# radio_module.net
KiCad netlist of a schematic drawn in Altium Designer
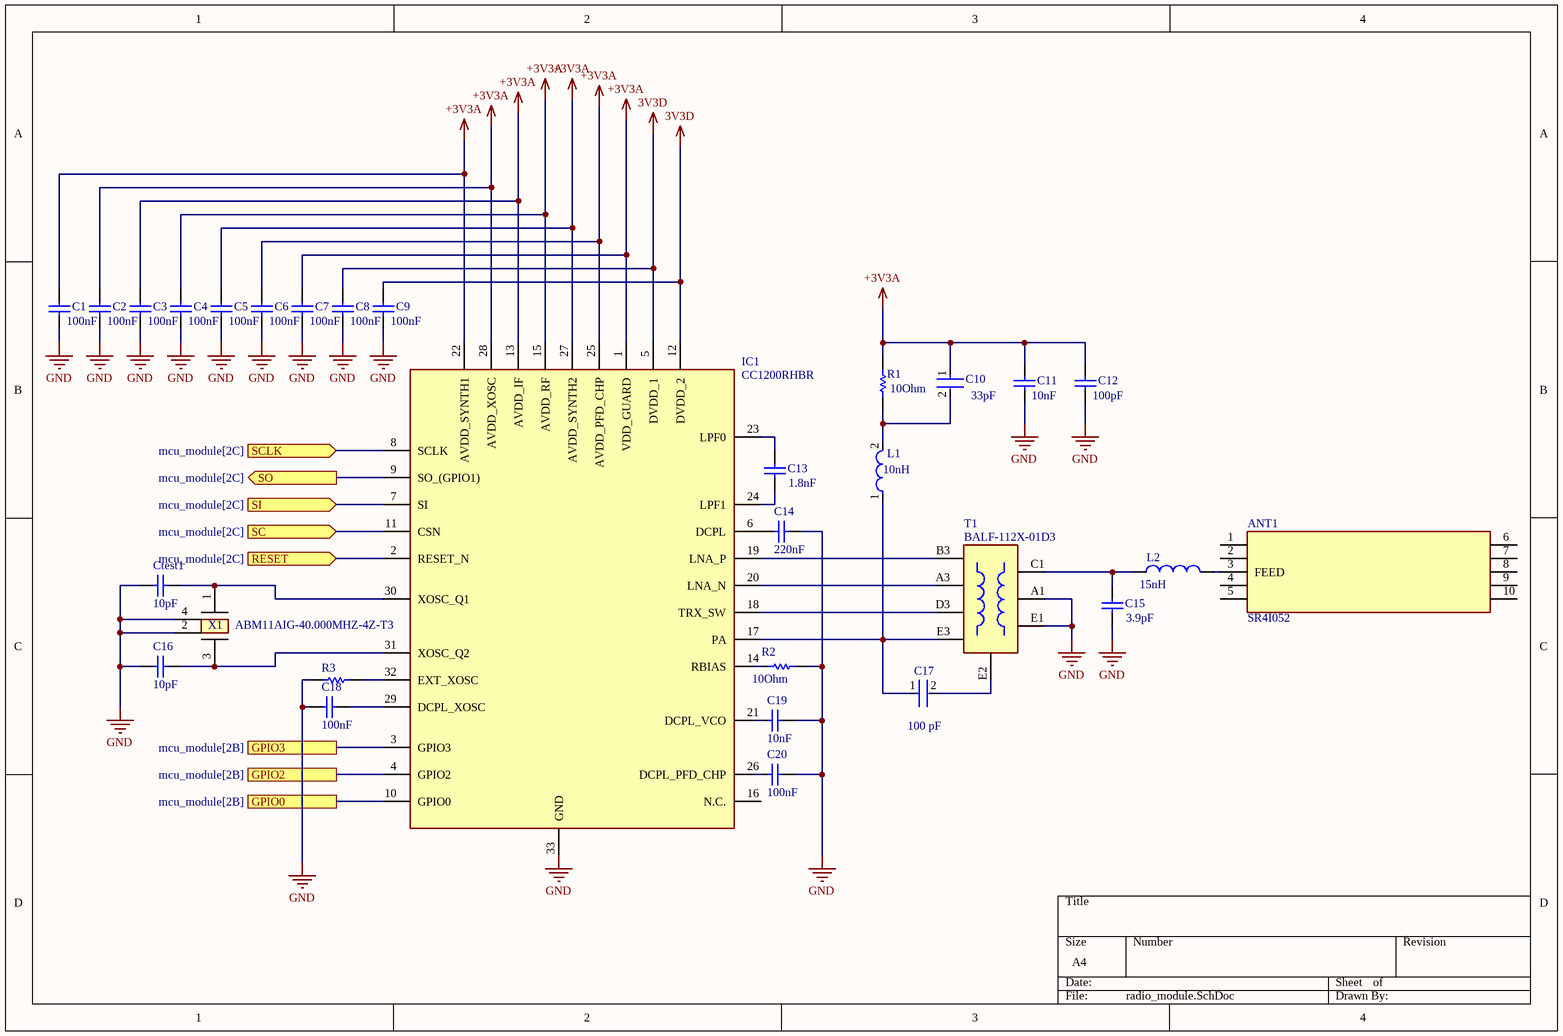
[diagram p0: radio_module.SchDoc]

(export (version "E")
  (design (tool "Eeschema 10.0.6"))
  (components
    (comp (ref "ANT1")
      (value "SR4I052")
      (footprint "SamacSys:SR4I052")
      (description "Antenna")
      (fields (field (name "MOUSER PART NUMBER") "237-SR4I052"))
      (libsource (lib "*") (part "SR4I052"))
    )
    (comp (ref "C1")
      (value "100nF")
      (footprint "CAPC1608X92X38LL15T08")
      (fields (field (name "MANUFACTURER") "Vitramon") (field (name "PART NUMBER") "VJ0603D3R9CXPAJ"))
      (libsource (lib "Altium Content Vault") (part "CAP"))
    )
    (comp (ref "C2")
      (value "100nF")
      (footprint "CAPC1608X92X38LL15T08")
      (fields (field (name "MANUFACTURER") "Vitramon") (field (name "PART NUMBER") "VJ0603D3R9CXPAJ"))
      (libsource (lib "Altium Content Vault") (part "CAP"))
    )
    (comp (ref "C3")
      (value "100nF")
      (footprint "CAPC1608X92X38LL15T08")
      (fields (field (name "MANUFACTURER") "Vitramon") (field (name "PART NUMBER") "VJ0603D3R9CXPAJ"))
      (libsource (lib "Altium Content Vault") (part "CAP"))
    )
    (comp (ref "C4")
      (value "100nF")
      (footprint "CAPC1608X92X38LL15T08")
      (fields (field (name "MANUFACTURER") "Vitramon") (field (name "PART NUMBER") "VJ0603D3R9CXPAJ"))
      (libsource (lib "Altium Content Vault") (part "CAP"))
    )
    (comp (ref "C5")
      (value "100nF")
      (footprint "CAPC1608X92X38LL15T08")
      (fields (field (name "MANUFACTURER") "Vitramon") (field (name "PART NUMBER") "VJ0603D3R9CXPAJ"))
      (libsource (lib "Altium Content Vault") (part "CAP"))
    )
    (comp (ref "C6")
      (value "100nF")
      (footprint "CAPC1608X92X38LL15T08")
      (fields (field (name "MANUFACTURER") "Vitramon") (field (name "PART NUMBER") "VJ0603D3R9CXPAJ"))
      (libsource (lib "Altium Content Vault") (part "CAP"))
    )
    (comp (ref "C7")
      (value "100nF")
      (footprint "CAPC1608X92X38LL15T08")
      (fields (field (name "MANUFACTURER") "Vitramon") (field (name "PART NUMBER") "VJ0603D3R9CXPAJ"))
      (libsource (lib "Altium Content Vault") (part "CAP"))
    )
    (comp (ref "C8")
      (value "100nF")
      (footprint "CAPC1608X92X38LL15T08")
      (fields (field (name "MANUFACTURER") "Vitramon") (field (name "PART NUMBER") "VJ0603D3R9CXPAJ"))
      (libsource (lib "Altium Content Vault") (part "CAP"))
    )
    (comp (ref "C9")
      (value "100nF")
      (footprint "CAPC1608X92X38LL15T08")
      (fields (field (name "MANUFACTURER") "Vitramon") (field (name "PART NUMBER") "VJ0603D3R9CXPAJ"))
      (libsource (lib "Altium Content Vault") (part "CAP"))
    )
    (comp (ref "C10")
      (value "33pF")
      (footprint "FP-C0402-BB-MFG")
      (description "CAP CER 0.1UF 16V X7R 0402")
      (fields
        (field (name "TOLERANCE") "0.1")
        (field (name "OCTOPART") "https://octopart.com/c0402c104k4ractu-kemet-94158")
      )
      (libsource (lib "Altium Content Vault") (part "b4654b650e69147ec39a6b967a45e02"))
    )
    (comp (ref "C11")
      (value "10nF")
      (footprint "CAPC1608X92X38LL15T08")
      (fields (field (name "MANUFACTURER") "Vitramon") (field (name "PART NUMBER") "VJ0603D3R9CXPAJ"))
      (libsource (lib "Altium Content Vault") (part "CAP"))
    )
    (comp (ref "C12")
      (value "100pF")
      (footprint "CAPC1608X92X38LL15T08")
      (fields (field (name "MANUFACTURER") "Vitramon") (field (name "PART NUMBER") "VJ0603D3R9CXPAJ"))
      (libsource (lib "Altium Content Vault") (part "CAP"))
    )
    (comp (ref "C13")
      (value "1.8nF")
      (footprint "CAPC1608X92X38LL15T08")
      (fields (field (name "MANUFACTURER") "Vitramon") (field (name "PART NUMBER") "VJ0603D3R9CXPAJ"))
      (libsource (lib "Altium Content Vault") (part "CAP"))
    )
    (comp (ref "C14")
      (value "220nF")
      (footprint "CAPC1608X92X38LL15T08")
      (fields (field (name "MANUFACTURER") "Vitramon") (field (name "PART NUMBER") "VJ0603D3R9CXPAJ"))
      (libsource (lib "Altium Content Vault") (part "CAP"))
    )
    (comp (ref "C15")
      (value "3.9pF")
      (footprint "CAPC1608X92X38LL15T08")
      (fields (field (name "MANUFACTURER") "Vitramon") (field (name "PART NUMBER") "VJ0603D3R9CXPAJ"))
      (libsource (lib "Altium Content Vault") (part "CAP"))
    )
    (comp (ref "C16")
      (value "10pF")
      (footprint "CAPC1608X92X38LL15T08")
      (fields (field (name "MANUFACTURER") "Vitramon") (field (name "PART NUMBER") "VJ0603D3R9CXPAJ"))
      (libsource (lib "Altium Content Vault") (part "CAP"))
    )
    (comp (ref "C17")
      (value "C0402C101J5GACTU")
      (footprint "FP-C0402-BB-MFG")
      (description "CAP CER 100PF 50V C0G/NP0 0402")
      (fields
        (field (name "MANUFACTURER") "Kemet")
        (field (name "TOLERANCE") "0.05")
        (field (name "CAPACITANCE") "100 pF")
      )
      (libsource (lib "Altium Content Vault") (part "b4654b650e69147ec39a6b967a45e02"))
    )
    (comp (ref "C18")
      (value "100nF")
      (footprint "CAPC1608X92X38LL15T08")
      (fields (field (name "MANUFACTURER") "Vitramon") (field (name "PART NUMBER") "VJ0603D3R9CXPAJ"))
      (libsource (lib "Altium Content Vault") (part "CAP"))
    )
    (comp (ref "C19")
      (value "10nF")
      (footprint "CAPC1608X92X38LL15T08")
      (fields (field (name "MANUFACTURER") "Vitramon") (field (name "PART NUMBER") "VJ0603D3R9CXPAJ"))
      (libsource (lib "Altium Content Vault") (part "CAP"))
    )
    (comp (ref "C20")
      (value "100nF")
      (footprint "CAPC1608X92X38LL15T08")
      (fields (field (name "MANUFACTURER") "Vitramon") (field (name "PART NUMBER") "VJ0603D3R9CXPAJ"))
      (libsource (lib "Altium Content Vault") (part "CAP"))
    )
    (comp (ref "Ctest1")
      (value "10pF")
      (footprint "CAPC1608X92X38LL15T08")
      (fields (field (name "MANUFACTURER") "Vitramon") (field (name "PART NUMBER") "VJ0603D3R9CXPAJ"))
      (libsource (lib "Altium Content Vault") (part "CAP"))
    )
    (comp (ref "IC1")
      (value "CC1200RHBR")
      (footprint "SamacSys:QFN50P500X500X100-33N-D")
      (description "Integrated Circuit")
      (fields (field (name "MOUSER PART NUMBER") "595-CC1200RHBR"))
      (libsource (lib "SamacSys") (part "CC1200RHBR"))
    )
    (comp (ref "L1")
      (value "LQW15AN10NH00D")
      (footprint "FP-LQW15AN_00-W0_6-0_1-MFG")
      (description "Wire Wound RF Inductor 10nH ±3% 500mA 0.17Ω 0402 (1005)")
      (fields (field (name "INDUCTANCE") "10nH") (field (name "TOLERANCE") "3%"))
      (libsource (lib "Altium Content Vault") (part "725321dda6339637d4d059423bc1c3c"))
    )
    (comp (ref "L2")
      (value "7447860115G")
      (footprint "WE-MK_0603_L1.6W0.8H0.8")
      (description "7447860115G Multilayer Inductor, 15Nh, 0.3A, 0603 Rohs Compliant: Yes")
      (fields (field (name "INDUCTANCE") "15nH"))
      (libsource (lib "Altium Content Vault") (part "Inductor - 1"))
    )
    (comp (ref "R1")
      (value "10Ohm")
      (footprint "RESC1005X40X25NL05T05")
      (fields (field (name "PART NUMBER") "CRCW040210R0FKED") (field (name "MANUFACTURER") "Vishay Dale"))
      (libsource (lib "Altium Content Vault") (part "RES"))
    )
    (comp (ref "R2")
      (value "RC0603JR-070RL")
      (footprint "RESC1608X55X25ML10T15")
      (description "Chip Resistor, 0 Ohm, +/- 5%, 0.1 W, -55 to 155 degC, 0603 (1608 Metric), RoHS, Tape and Reel")
      (fields
        (field (name "TOLERANCE") "5%")
        (field (name "RESISTANCE") "10Ohm")
        (field (name "MANUFACTURER") "Yageo")
      )
      (libsource (lib "Altium Content Vault") (part "RES-2"))
    )
    (comp (ref "R3")
      (value "RC0603JR-070RL")
      (footprint "RESC1608X55X25ML10T15")
      (description "Chip Resistor, 0 Ohm, +/- 5%, 0.1 W, -55 to 155 degC, 0603 (1608 Metric), RoHS, Tape and Reel")
      (fields (field (name "TOLERANCE") "5%") (field (name "MANUFACTURER") "Yageo"))
      (libsource (lib "Altium Content Vault") (part "RES-2"))
    )
    (comp (ref "T1")
      (value "BALF-112X-01D3")
      (footprint "SamacSys:BALF112X01D3")
      (description "Transformer")
      (fields (field (name "MOUSER PART NUMBER") "511-BALF-112X-01D3"))
      (libsource (lib "SamacSys") (part "BALF-112X-01D3"))
    )
    (comp (ref "X1")
      (value "ABM11AIG-40.000MHZ-4Z-T3")
      (footprint "SamacSys:ABM11AIG16000MHZ81ZT")
      (description "Crystal or Oscillator")
      (fields (field (name "MOUSER PART NUMBER") "815-M11AIG-40-4ZT3"))
      (libsource (lib "SamacSys") (part "ABM11AIG-40.000MHZ-4Z-T3"))
    )
  )
  (nets
    (net (code "1") (name "+3V3A") (class "Default")
      (node (ref "C1") (pin "2") (pinfunction "2_2") (pintype "passive"))
      (node (ref "C10") (pin "1") (pinfunction "1_1") (pintype "passive"))
      (node (ref "C11") (pin "2") (pinfunction "2_2") (pintype "passive"))
      (node (ref "C12") (pin "2") (pinfunction "2_2") (pintype "passive"))
      (node (ref "C2") (pin "2") (pinfunction "2_2") (pintype "passive"))
      (node (ref "C3") (pin "2") (pinfunction "2_2") (pintype "passive"))
      (node (ref "C4") (pin "2") (pinfunction "2_2") (pintype "passive"))
      (node (ref "C5") (pin "2") (pinfunction "2_2") (pintype "passive"))
      (node (ref "C6") (pin "2") (pinfunction "2_2") (pintype "passive"))
      (node (ref "C7") (pin "2") (pinfunction "2_2") (pintype "passive"))
      (node (ref "IC1") (pin "1") (pinfunction "VDD_GUARD_1") (pintype "passive"))
      (node (ref "IC1") (pin "13") (pinfunction "AVDD_IF_13") (pintype "passive"))
      (node (ref "IC1") (pin "15") (pinfunction "AVDD_RF_15") (pintype "passive"))
      (node (ref "IC1") (pin "22") (pinfunction "AVDD_SYNTH1_22") (pintype "passive"))
      (node (ref "IC1") (pin "25") (pinfunction "AVDD_PFD_CHP_25") (pintype "passive"))
      (node (ref "IC1") (pin "27") (pinfunction "AVDD_SYNTH2_27") (pintype "passive"))
      (node (ref "IC1") (pin "28") (pinfunction "AVDD_XOSC_28") (pintype "passive"))
      (node (ref "R1") (pin "2") (pinfunction "2_2") (pintype "passive"))
    )
    (net (code "2") (name "/GPIO0") (class "Default")
      (node (ref "IC1") (pin "10") (pinfunction "GPIO0_10") (pintype "passive"))
    )
    (net (code "3") (name "/GPIO2") (class "Default")
      (node (ref "IC1") (pin "4") (pinfunction "GPIO2_4") (pintype "passive"))
    )
    (net (code "4") (name "/GPIO3") (class "Default")
      (node (ref "IC1") (pin "3") (pinfunction "GPIO3_3") (pintype "passive"))
    )
    (net (code "5") (name "/RESET") (class "Default")
      (node (ref "IC1") (pin "2") (pinfunction "RESET_N_2") (pintype "passive"))
    )
    (net (code "6") (name "/SC") (class "Default")
      (node (ref "IC1") (pin "11") (pinfunction "CSN_11") (pintype "passive"))
    )
    (net (code "7") (name "/SCLK") (class "Default")
      (node (ref "IC1") (pin "8") (pinfunction "SCLK_8") (pintype "passive"))
    )
    (net (code "8") (name "/SI") (class "Default")
      (node (ref "IC1") (pin "7") (pinfunction "SI_7") (pintype "passive"))
    )
    (net (code "9") (name "/SO") (class "Default")
      (node (ref "IC1") (pin "9") (pinfunction "SO_(GPIO1)_9") (pintype "passive"))
    )
    (net (code "10") (name "3V3D") (class "Default")
      (node (ref "C8") (pin "2") (pinfunction "2_2") (pintype "passive"))
      (node (ref "C9") (pin "2") (pinfunction "2_2") (pintype "passive"))
      (node (ref "IC1") (pin "12") (pinfunction "DVDD_2_12") (pintype "passive"))
      (node (ref "IC1") (pin "5") (pinfunction "DVDD_1_5") (pintype "passive"))
    )
    (net (code "11") (name "GND") (class "Default")
      (node (ref "C1") (pin "1") (pinfunction "1_1") (pintype "passive"))
      (node (ref "C11") (pin "1") (pinfunction "1_1") (pintype "passive"))
      (node (ref "C12") (pin "1") (pinfunction "1_1") (pintype "passive"))
      (node (ref "C14") (pin "2") (pinfunction "2_2") (pintype "passive"))
      (node (ref "C15") (pin "1") (pinfunction "1_1") (pintype "passive"))
      (node (ref "C16") (pin "2") (pinfunction "2_2") (pintype "passive"))
      (node (ref "C18") (pin "2") (pinfunction "2_2") (pintype "passive"))
      (node (ref "C19") (pin "1") (pinfunction "1_1") (pintype "passive"))
      (node (ref "C2") (pin "1") (pinfunction "1_1") (pintype "passive"))
      (node (ref "C20") (pin "1") (pinfunction "1_1") (pintype "passive"))
      (node (ref "C3") (pin "1") (pinfunction "1_1") (pintype "passive"))
      (node (ref "C4") (pin "1") (pinfunction "1_1") (pintype "passive"))
      (node (ref "C5") (pin "1") (pinfunction "1_1") (pintype "passive"))
      (node (ref "C6") (pin "1") (pinfunction "1_1") (pintype "passive"))
      (node (ref "C7") (pin "1") (pinfunction "1_1") (pintype "passive"))
      (node (ref "C8") (pin "1") (pinfunction "1_1") (pintype "passive"))
      (node (ref "C9") (pin "1") (pinfunction "1_1") (pintype "passive"))
      (node (ref "Ctest1") (pin "2") (pinfunction "2_2") (pintype "passive"))
      (node (ref "IC1") (pin "33") (pinfunction "GND_33") (pintype "passive"))
      (node (ref "R2") (pin "2") (pinfunction "2_2") (pintype "passive"))
      (node (ref "R3") (pin "1") (pinfunction "1_1") (pintype "passive"))
      (node (ref "T1") (pin "A1") (pinfunction "GND_1_A1") (pintype "passive"))
      (node (ref "T1") (pin "E1") (pinfunction "GND_2_E1") (pintype "passive"))
      (node (ref "X1") (pin "2") (pinfunction "GND_1_2") (pintype "passive"))
      (node (ref "X1") (pin "4") (pinfunction "GND_2_4") (pintype "passive"))
    )
    (net (code "12") (name "Net-(ANT1-FEED)") (class "Default")
      (node (ref "ANT1") (pin "3") (pinfunction "FEED_3") (pintype "passive"))
      (node (ref "L2") (pin "2") (pinfunction "2_2") (pintype "passive"))
    )
    (net (code "13") (name "Net-(C10-Pad2)") (class "Default")
      (node (ref "C10") (pin "2") (pinfunction "2_2") (pintype "passive"))
      (node (ref "L1") (pin "2") (pinfunction "2_2") (pintype "passive"))
      (node (ref "R1") (pin "1") (pinfunction "1_1") (pintype "passive"))
    )
    (net (code "14") (name "Net-(IC1-DCPL)") (class "Default")
      (node (ref "C14") (pin "1") (pinfunction "1_1") (pintype "passive"))
      (node (ref "IC1") (pin "6") (pinfunction "DCPL_6") (pintype "passive"))
    )
    (net (code "15") (name "Net-(IC1-DCPL_PFD_CHP)") (class "Default")
      (node (ref "C20") (pin "2") (pinfunction "2_2") (pintype "passive"))
      (node (ref "IC1") (pin "26") (pinfunction "DCPL_PFD_CHP_26") (pintype "passive"))
    )
    (net (code "16") (name "Net-(IC1-DCPL_VCO)") (class "Default")
      (node (ref "C19") (pin "2") (pinfunction "2_2") (pintype "passive"))
      (node (ref "IC1") (pin "21") (pinfunction "DCPL_VCO_21") (pintype "passive"))
    )
    (net (code "17") (name "Net-(IC1-DCPL_XOSC)") (class "Default")
      (node (ref "C18") (pin "1") (pinfunction "1_1") (pintype "passive"))
      (node (ref "IC1") (pin "29") (pinfunction "DCPL_XOSC_29") (pintype "passive"))
    )
    (net (code "18") (name "Net-(IC1-EXT_XOSC)") (class "Default")
      (node (ref "IC1") (pin "32") (pinfunction "EXT_XOSC_32") (pintype "passive"))
      (node (ref "R3") (pin "2") (pinfunction "2_2") (pintype "passive"))
    )
    (net (code "19") (name "Net-(IC1-LNA_N)") (class "Default")
      (node (ref "IC1") (pin "20") (pinfunction "LNA_N_20") (pintype "passive"))
      (node (ref "T1") (pin "A3") (pinfunction "LNA-_A3") (pintype "passive"))
    )
    (net (code "20") (name "Net-(IC1-LNA_P)") (class "Default")
      (node (ref "IC1") (pin "19") (pinfunction "LNA_P_19") (pintype "passive"))
      (node (ref "T1") (pin "B3") (pinfunction "LNA+_B3") (pintype "passive"))
    )
    (net (code "21") (name "Net-(IC1-LPF0)") (class "Default")
      (node (ref "C13") (pin "2") (pinfunction "2_2") (pintype "passive"))
      (node (ref "IC1") (pin "23") (pinfunction "LPF0_23") (pintype "passive"))
    )
    (net (code "22") (name "Net-(IC1-LPF1)") (class "Default")
      (node (ref "C13") (pin "1") (pinfunction "1_1") (pintype "passive"))
      (node (ref "IC1") (pin "24") (pinfunction "LPF1_24") (pintype "passive"))
    )
    (net (code "23") (name "Net-(IC1-PA)") (class "Default")
      (node (ref "C17") (pin "1") (pinfunction "1_1") (pintype "passive"))
      (node (ref "IC1") (pin "17") (pinfunction "PA_17") (pintype "passive"))
      (node (ref "L1") (pin "1") (pinfunction "1_1") (pintype "passive"))
      (node (ref "T1") (pin "E3") (pinfunction "PA_OUT_E3") (pintype "passive"))
    )
    (net (code "24") (name "Net-(IC1-RBIAS)") (class "Default")
      (node (ref "IC1") (pin "14") (pinfunction "RBIAS_14") (pintype "passive"))
      (node (ref "R2") (pin "1") (pinfunction "1_1") (pintype "passive"))
    )
    (net (code "25") (name "Net-(IC1-TRX_SW)") (class "Default")
      (node (ref "IC1") (pin "18") (pinfunction "TRX_SW_18") (pintype "passive"))
      (node (ref "T1") (pin "D3") (pinfunction "TRX_SWITCH_D3") (pintype "passive"))
    )
    (net (code "26") (name "Net-(IC1-XOSC_Q1)") (class "Default")
      (node (ref "Ctest1") (pin "1") (pinfunction "1_1") (pintype "passive"))
      (node (ref "IC1") (pin "30") (pinfunction "XOSC_Q1_30") (pintype "passive"))
      (node (ref "X1") (pin "1") (pinfunction "X1_1") (pintype "passive"))
    )
    (net (code "27") (name "Net-(IC1-XOSC_Q2)") (class "Default")
      (node (ref "C16") (pin "1") (pinfunction "1_1") (pintype "passive"))
      (node (ref "IC1") (pin "31") (pinfunction "XOSC_Q2_31") (pintype "passive"))
      (node (ref "X1") (pin "3") (pinfunction "X2_3") (pintype "passive"))
    )
    (net (code "28") (name "Net-(T1-ANT)") (class "Default")
      (node (ref "C15") (pin "2") (pinfunction "2_2") (pintype "passive"))
      (node (ref "L2") (pin "1") (pinfunction "1_1") (pintype "passive"))
      (node (ref "T1") (pin "C1") (pinfunction "ANT_C1") (pintype "passive"))
    )
    (net (code "29") (name "Net-(T1-PA_C)") (class "Default")
      (node (ref "C17") (pin "2") (pinfunction "2_2") (pintype "passive"))
      (node (ref "T1") (pin "E2") (pinfunction "PA_C_E2") (pintype "passive"))
    )
    (net (code "30") (name "unconnected-(ANT1-NOT_CONNECTED_1-Pad1)") (class "Default")
      (node (ref "ANT1") (pin "1") (pinfunction "NOT_CONNECTED_1_1") (pintype "passive"))
    )
    (net (code "31") (name "unconnected-(ANT1-NOT_CONNECTED_2-Pad2)") (class "Default")
      (node (ref "ANT1") (pin "2") (pinfunction "NOT_CONNECTED_2_2") (pintype "passive"))
    )
    (net (code "32") (name "unconnected-(ANT1-NOT_CONNECTED_3-Pad4)") (class "Default")
      (node (ref "ANT1") (pin "4") (pinfunction "NOT_CONNECTED_3_4") (pintype "passive"))
    )
    (net (code "33") (name "unconnected-(ANT1-NOT_CONNECTED_4-Pad5)") (class "Default")
      (node (ref "ANT1") (pin "5") (pinfunction "NOT_CONNECTED_4_5") (pintype "passive"))
    )
    (net (code "34") (name "unconnected-(ANT1-NOT_CONNECTED_5-Pad6)") (class "Default")
      (node (ref "ANT1") (pin "6") (pinfunction "NOT_CONNECTED_5_6") (pintype "passive"))
    )
    (net (code "35") (name "unconnected-(ANT1-NOT_CONNECTED_6-Pad7)") (class "Default")
      (node (ref "ANT1") (pin "7") (pinfunction "NOT_CONNECTED_6_7") (pintype "passive"))
    )
    (net (code "36") (name "unconnected-(ANT1-NOT_CONNECTED_7-Pad8)") (class "Default")
      (node (ref "ANT1") (pin "8") (pinfunction "NOT_CONNECTED_7_8") (pintype "passive"))
    )
    (net (code "37") (name "unconnected-(ANT1-NOT_CONNECTED_8-Pad9)") (class "Default")
      (node (ref "ANT1") (pin "9") (pinfunction "NOT_CONNECTED_8_9") (pintype "passive"))
    )
    (net (code "38") (name "unconnected-(ANT1-NOT_CONNECTED_9-Pad10)") (class "Default")
      (node (ref "ANT1") (pin "10") (pinfunction "NOT_CONNECTED_9_10") (pintype "passive"))
    )
    (net (code "39") (name "unconnected-(IC1-N.C.-Pad16)") (class "Default")
      (node (ref "IC1") (pin "16") (pinfunction "N.C._16") (pintype "passive"))
    )
  )
)
